# design.net
KiCad netlist of a schematic drawn in Altium Designer
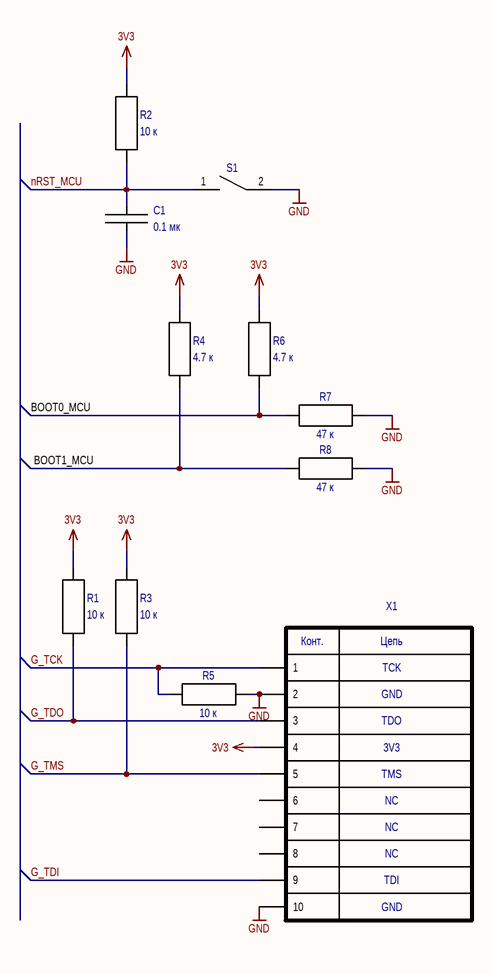
[diagram p0: служебный.SchDoc]

(export (version "E")
  (design (tool "Eeschema 10.0.6"))
  (components
    (comp (ref "C1")
      (value "0.1 мк")
      (fields (field (name "Comment") "0.1 мкФ ±* * * *, *"))
      (libsource (lib "Lisaveta") (part "C"))
    )
    (comp (ref "R1")
      (value "10 к")
      (fields (field (name "Comment") "10 кОм ±* *, *"))
      (libsource (lib "Lisaveta") (part "R_1"))
    )
    (comp (ref "R2")
      (value "10 к")
      (fields (field (name "Comment") "10 кОм ±* *, *"))
      (libsource (lib "Lisaveta") (part "R_1"))
    )
    (comp (ref "R3")
      (value "10 к")
      (fields (field (name "Comment") "10 кОм ±* *, *"))
      (libsource (lib "Lisaveta") (part "R_1"))
    )
    (comp (ref "R4")
      (value "4.7 к")
      (fields (field (name "Comment") "4.7 кОм ±* *, *"))
      (libsource (lib "Lisaveta") (part "R_1"))
    )
    (comp (ref "R5")
      (value "10 к")
      (fields (field (name "Comment") "10 кОм ±* *, *"))
      (libsource (lib "Lisaveta") (part "R_1"))
    )
    (comp (ref "R6")
      (value "4.7 к")
      (fields (field (name "Comment") "4.7 кОм ±* *, *"))
      (libsource (lib "Lisaveta") (part "R_1"))
    )
    (comp (ref "R7")
      (value "47 к")
      (fields (field (name "Comment") "47 кОм ±* *, *"))
      (libsource (lib "Lisaveta") (part "R_1"))
    )
    (comp (ref "R8")
      (value "47 к")
      (fields (field (name "Comment") "47 кОм ±* *, *"))
      (libsource (lib "Lisaveta") (part "R_1"))
    )
    (comp (ref "S1")
      (value "Тактильный переключатель KLS7-TS6604-4.3-180-B KLS")
      (fields (field (name "PARTNUMBER") "KLS7-TS6604-4.3-180-B"))
      (libsource (lib "Lisaveta") (part "BTN"))
    )
    (comp (ref "X1")
      (value "KONT_POLE_JTAG14")
      (fields
        (field (name "1") "GND")
        (field (name "2") "3V3")
        (field (name "4") "TMS")
        (field (name "6") "TCK")
        (field (name "8") "TDO")
        (field (name "10") "TDI")
        (field (name "12") "NC")
        (field (name "14") "NC")
        (field (name "5") "NC")
        (field (name "9") "GND")
      )
      (libsource (lib "Lisaveta") (part "KONT_POLE_JTAG10"))
    )
  )
  (nets
    (net (code "1") (name "/BOOT0_MCU") (class "Default")
      (node (ref "R6") (pin "2") (pinfunction "2_2") (pintype "passive"))
      (node (ref "R7") (pin "1") (pinfunction "1_1") (pintype "passive"))
    )
    (net (code "2") (name "/BOOT1_MCU") (class "Default")
      (node (ref "R4") (pin "2") (pinfunction "2_2") (pintype "passive"))
      (node (ref "R8") (pin "1") (pinfunction "1_1") (pintype "passive"))
    )
    (net (code "3") (name "/G_TCK") (class "Default")
      (node (ref "R5") (pin "1") (pinfunction "1_1") (pintype "passive"))
      (node (ref "X1") (pin "1") (pinfunction "1_1") (pintype "passive"))
    )
    (net (code "4") (name "/G_TDI") (class "Default")
      (node (ref "X1") (pin "9") (pinfunction "9_9") (pintype "passive"))
    )
    (net (code "5") (name "/G_TDO") (class "Default")
      (node (ref "R1") (pin "2") (pinfunction "2_2") (pintype "passive"))
      (node (ref "X1") (pin "3") (pinfunction "3_3") (pintype "passive"))
    )
    (net (code "6") (name "/G_TMS") (class "Default")
      (node (ref "R3") (pin "2") (pinfunction "2_2") (pintype "passive"))
      (node (ref "X1") (pin "5") (pinfunction "5_5") (pintype "passive"))
    )
    (net (code "7") (name "/nRST_MCU") (class "Default")
      (node (ref "C1") (pin "2") (pinfunction "2_2") (pintype "passive"))
      (node (ref "R2") (pin "2") (pinfunction "2_2") (pintype "passive"))
      (node (ref "S1") (pin "1") (pinfunction "1_1") (pintype "passive"))
    )
    (net (code "8") (name "3V3") (class "Default")
      (node (ref "R1") (pin "1") (pinfunction "1_1") (pintype "passive"))
      (node (ref "R2") (pin "1") (pinfunction "1_1") (pintype "passive"))
      (node (ref "R3") (pin "1") (pinfunction "1_1") (pintype "passive"))
      (node (ref "R4") (pin "1") (pinfunction "1_1") (pintype "passive"))
      (node (ref "R6") (pin "1") (pinfunction "1_1") (pintype "passive"))
      (node (ref "X1") (pin "4") (pinfunction "4_4") (pintype "passive"))
    )
    (net (code "9") (name "GND") (class "Default")
      (node (ref "C1") (pin "1") (pinfunction "1_1") (pintype "passive"))
      (node (ref "R5") (pin "2") (pinfunction "2_2") (pintype "passive"))
      (node (ref "R7") (pin "2") (pinfunction "2_2") (pintype "passive"))
      (node (ref "R8") (pin "2") (pinfunction "2_2") (pintype "passive"))
      (node (ref "S1") (pin "2") (pinfunction "2_2") (pintype "passive"))
      (node (ref "X1") (pin "10") (pinfunction "10_10") (pintype "passive"))
      (node (ref "X1") (pin "2") (pinfunction "2_2") (pintype "passive"))
    )
    (net (code "10") (name "unconnected-(X1-Pad6)") (class "Default")
      (node (ref "X1") (pin "6") (pinfunction "6_6") (pintype "passive"))
    )
    (net (code "11") (name "unconnected-(X1-Pad7)") (class "Default")
      (node (ref "X1") (pin "7") (pinfunction "7_7") (pintype "passive"))
    )
    (net (code "12") (name "unconnected-(X1-Pad8)") (class "Default")
      (node (ref "X1") (pin "8") (pinfunction "8_8") (pintype "passive"))
    )
  )
)
